# RoverMuxJig.net
KiCad netlist of a schematic drawn in EAGLE
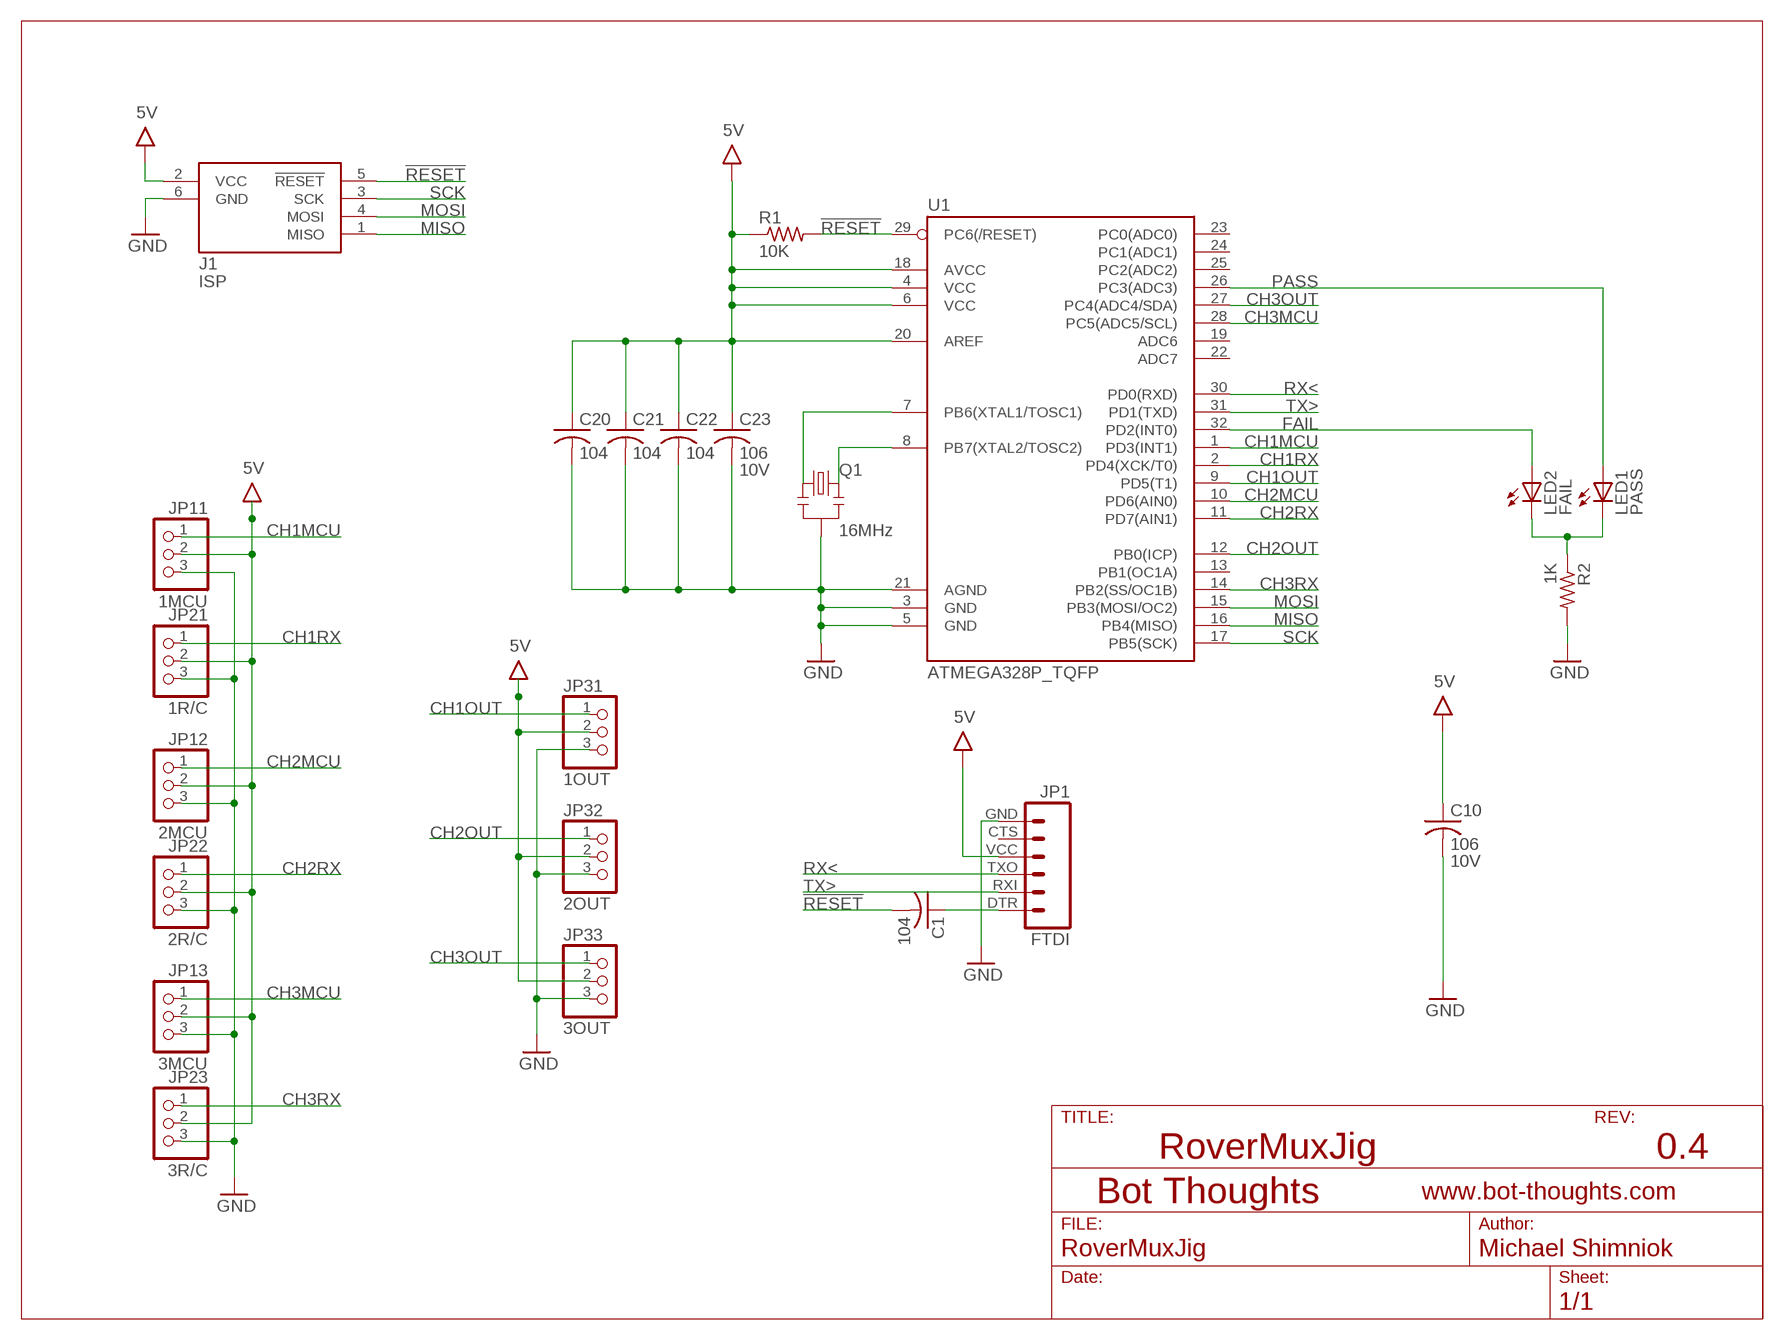
[diagram p0: schematic, sheet 1]

(export (version "E")
  (design (tool "Eeschema 10.0.6"))
  (components
    (comp (ref "C1")
      (value "104")
      (footprint "eagle-import:C0603")
      (fields (field (name "PARTNO") "C1608X7R1E104K080AA"))
      (libsource (lib "eagle-import") (part "C-USC0603"))
    )
    (comp (ref "C10")
      (value "106")
      (footprint "eagle-import:C0603")
      (fields (field (name "PARTNO") "CL10A106MP8NNNC") (field (name "VOLTAGE") "10V"))
      (libsource (lib "eagle-import") (part "C-USC0603"))
    )
    (comp (ref "C20")
      (value "104")
      (footprint "eagle-import:C0603")
      (fields (field (name "PARTNO") "C1608X7R1E104K080AA"))
      (libsource (lib "eagle-import") (part "C-USC0603"))
    )
    (comp (ref "C21")
      (value "104")
      (footprint "eagle-import:C0603")
      (fields (field (name "PARTNO") "C1608X7R1E104K080AA"))
      (libsource (lib "eagle-import") (part "C-USC0603"))
    )
    (comp (ref "C22")
      (value "104")
      (footprint "eagle-import:C0603")
      (fields (field (name "PARTNO") "C1608X7R1E104K080AA"))
      (libsource (lib "eagle-import") (part "C-USC0603"))
    )
    (comp (ref "C23")
      (value "106")
      (footprint "eagle-import:C0603")
      (fields (field (name "PARTNO") "CL10A106MP8NNNC") (field (name "VOLTAGE") "10V"))
      (libsource (lib "eagle-import") (part "C-USC0603"))
    )
    (comp (ref "J1")
      (value "ISP")
      (footprint "eagle-import:CON6P2R")
      (libsource (lib "eagle-import") (part "AVRISP6"))
    )
    (comp (ref "JP1")
      (value "FTDI")
      (footprint "eagle-import:FTDI_BASIC")
      (libsource (lib "eagle-import") (part "FTDI_BASICPTH"))
    )
    (comp (ref "JP11")
      (value "1MCU")
      (footprint "eagle-import:1X03-S")
      (libsource (lib "eagle-import") (part "PINHD-1X03_2.54-S"))
    )
    (comp (ref "JP12")
      (value "2MCU")
      (footprint "eagle-import:1X03-S")
      (libsource (lib "eagle-import") (part "PINHD-1X03_2.54-S"))
    )
    (comp (ref "JP13")
      (value "3MCU")
      (footprint "eagle-import:1X03-S")
      (libsource (lib "eagle-import") (part "PINHD-1X03_2.54-S"))
    )
    (comp (ref "JP21")
      (value "1R/C")
      (footprint "eagle-import:1X03-S")
      (libsource (lib "eagle-import") (part "PINHD-1X03_2.54-S"))
    )
    (comp (ref "JP22")
      (value "2R/C")
      (footprint "eagle-import:1X03-S")
      (libsource (lib "eagle-import") (part "PINHD-1X03_2.54-S"))
    )
    (comp (ref "JP23")
      (value "3R/C")
      (footprint "eagle-import:1X03-S")
      (libsource (lib "eagle-import") (part "PINHD-1X03_2.54-S"))
    )
    (comp (ref "JP31")
      (value "1OUT")
      (footprint "eagle-import:1X03-S")
      (libsource (lib "eagle-import") (part "PINHD-1X03_2.54-S"))
    )
    (comp (ref "JP32")
      (value "2OUT")
      (footprint "eagle-import:1X03-S")
      (libsource (lib "eagle-import") (part "PINHD-1X03_2.54-S"))
    )
    (comp (ref "JP33")
      (value "3OUT")
      (footprint "eagle-import:1X03-S")
      (libsource (lib "eagle-import") (part "PINHD-1X03_2.54-S"))
    )
    (comp (ref "LED1")
      (value "PASS")
      (footprint "eagle-import:CHIPLED_1206")
      (fields (field (name "PARTNO") "LH N974-KN-1"))
      (libsource (lib "eagle-import") (part "LEDCHIPLED_1206"))
    )
    (comp (ref "LED2")
      (value "FAIL")
      (footprint "eagle-import:CHIPLED_1206")
      (fields (field (name "PARTNO") "LG N971-KN-1"))
      (libsource (lib "eagle-import") (part "LEDCHIPLED_1206"))
    )
    (comp (ref "Q1")
      (value "16MHz")
      (footprint "eagle-import:CSTCE_V_C")
      (libsource (lib "eagle-import") (part "RESONATOR_CSTCE_V_C"))
    )
    (comp (ref "R1")
      (value "10K")
      (footprint "eagle-import:R0603")
      (fields (field (name "PARTNO") "RC0603JR-07330RL"))
      (libsource (lib "eagle-import") (part "R-US_R0603"))
    )
    (comp (ref "R2")
      (value "1K")
      (footprint "eagle-import:R0603")
      (fields (field (name "PARTNO") "RC0603JR-07330RL"))
      (libsource (lib "eagle-import") (part "R-US_R0603"))
    )
    (comp (ref "U1")
      (value "ATMEGA328P_TQFP")
      (footprint "eagle-import:TQFP32-08")
      (libsource (lib "eagle-import") (part "ATMEGA328P_TQFP"))
    )
  )
  (nets
    (net (code "1") (name "/CH1MCU") (class "Default")
      (node (ref "JP11") (pin "1") (pinfunction "1_1") (pintype "passive"))
      (node (ref "U1") (pin "1") (pinfunction "PD3(INT1)_1") (pintype "bidirectional"))
    )
    (net (code "2") (name "/CH1OUT") (class "Default")
      (node (ref "JP31") (pin "1") (pinfunction "1_1") (pintype "passive"))
      (node (ref "U1") (pin "9") (pinfunction "PD5(T1)_9") (pintype "bidirectional"))
    )
    (net (code "3") (name "/CH1RX") (class "Default")
      (node (ref "JP21") (pin "1") (pinfunction "1_1") (pintype "passive"))
      (node (ref "U1") (pin "2") (pinfunction "PD4(XCK/T0)_2") (pintype "bidirectional"))
    )
    (net (code "4") (name "/CH2MCU") (class "Default")
      (node (ref "JP12") (pin "1") (pinfunction "1_1") (pintype "passive"))
      (node (ref "U1") (pin "10") (pinfunction "PD6(AIN0)_10") (pintype "bidirectional"))
    )
    (net (code "5") (name "/CH2OUT") (class "Default")
      (node (ref "JP32") (pin "1") (pinfunction "1_1") (pintype "passive"))
      (node (ref "U1") (pin "12") (pinfunction "PB0(ICP)_12") (pintype "bidirectional"))
    )
    (net (code "6") (name "/CH2RX") (class "Default")
      (node (ref "JP22") (pin "1") (pinfunction "1_1") (pintype "passive"))
      (node (ref "U1") (pin "11") (pinfunction "PD7(AIN1)_11") (pintype "bidirectional"))
    )
    (net (code "7") (name "/CH3MCU") (class "Default")
      (node (ref "JP13") (pin "1") (pinfunction "1_1") (pintype "passive"))
      (node (ref "U1") (pin "28") (pinfunction "PC5(ADC5/SCL)_28") (pintype "bidirectional"))
    )
    (net (code "8") (name "/CH3OUT") (class "Default")
      (node (ref "JP33") (pin "1") (pinfunction "1_1") (pintype "passive"))
      (node (ref "U1") (pin "27") (pinfunction "PC4(ADC4/SDA)_27") (pintype "bidirectional"))
    )
    (net (code "9") (name "/CH3RX") (class "Default")
      (node (ref "JP23") (pin "1") (pinfunction "1_1") (pintype "passive"))
      (node (ref "U1") (pin "14") (pinfunction "PB2(SS/OC1B)_14") (pintype "bidirectional"))
    )
    (net (code "10") (name "/FAIL") (class "Default")
      (node (ref "LED2") (pin "A") (pinfunction "A_A") (pintype "passive"))
      (node (ref "U1") (pin "32") (pinfunction "PD2(INT0)_32") (pintype "bidirectional"))
    )
    (net (code "11") (name "/MISO") (class "Default")
      (node (ref "J1") (pin "1") (pinfunction "MISO_1") (pintype "input"))
      (node (ref "U1") (pin "16") (pinfunction "PB4(MISO)_16") (pintype "bidirectional"))
    )
    (net (code "12") (name "/MOSI") (class "Default")
      (node (ref "J1") (pin "4") (pinfunction "MOSI_4") (pintype "output"))
      (node (ref "U1") (pin "15") (pinfunction "PB3(MOSI/OC2)_15") (pintype "bidirectional"))
    )
    (net (code "13") (name "/PASS") (class "Default")
      (node (ref "LED1") (pin "A") (pinfunction "A_A") (pintype "passive"))
      (node (ref "U1") (pin "26") (pinfunction "PC3(ADC3)_26") (pintype "bidirectional"))
    )
    (net (code "14") (name "/RX<") (class "Default")
      (node (ref "JP1") (pin "TXO") (pinfunction "3_TXO") (pintype "passive"))
      (node (ref "U1") (pin "30") (pinfunction "PD0(RXD)_30") (pintype "bidirectional"))
    )
    (net (code "15") (name "/SCK") (class "Default")
      (node (ref "J1") (pin "3") (pinfunction "SCK_3") (pintype "output"))
      (node (ref "U1") (pin "17") (pinfunction "PB5(SCK)_17") (pintype "bidirectional"))
    )
    (net (code "16") (name "/TX>") (class "Default")
      (node (ref "JP1") (pin "RXI") (pinfunction "2_RXI") (pintype "passive"))
      (node (ref "U1") (pin "31") (pinfunction "PD1(TXD)_31") (pintype "bidirectional"))
    )
    (net (code "17") (name "/~{RESET}") (class "Default")
      (node (ref "C1") (pin "2") (pinfunction "2_2") (pintype "passive"))
      (node (ref "J1") (pin "5") (pinfunction "~{RESET}_5") (pintype "output"))
      (node (ref "R1") (pin "2") (pinfunction "2_2") (pintype "passive"))
      (node (ref "U1") (pin "29") (pinfunction "PC6(/RESET)_29") (pintype "bidirectional"))
    )
    (net (code "18") (name "5V") (class "Default")
      (node (ref "C10") (pin "1") (pinfunction "1_1") (pintype "passive"))
      (node (ref "C20") (pin "1") (pinfunction "1_1") (pintype "passive"))
      (node (ref "C21") (pin "1") (pinfunction "1_1") (pintype "passive"))
      (node (ref "C22") (pin "1") (pinfunction "1_1") (pintype "passive"))
      (node (ref "C23") (pin "1") (pinfunction "1_1") (pintype "passive"))
      (node (ref "J1") (pin "2") (pinfunction "VCC_2") (pintype "power_in"))
      (node (ref "JP1") (pin "VCC") (pinfunction "4_VCC") (pintype "passive"))
      (node (ref "JP11") (pin "2") (pinfunction "2_2") (pintype "passive"))
      (node (ref "JP12") (pin "2") (pinfunction "2_2") (pintype "passive"))
      (node (ref "JP13") (pin "2") (pinfunction "2_2") (pintype "passive"))
      (node (ref "JP21") (pin "2") (pinfunction "2_2") (pintype "passive"))
      (node (ref "JP22") (pin "2") (pinfunction "2_2") (pintype "passive"))
      (node (ref "JP23") (pin "2") (pinfunction "2_2") (pintype "passive"))
      (node (ref "JP31") (pin "2") (pinfunction "2_2") (pintype "passive"))
      (node (ref "JP32") (pin "2") (pinfunction "2_2") (pintype "passive"))
      (node (ref "JP33") (pin "2") (pinfunction "2_2") (pintype "passive"))
      (node (ref "R1") (pin "1") (pinfunction "1_1") (pintype "passive"))
      (node (ref "U1") (pin "18") (pinfunction "AVCC_18") (pintype "bidirectional"))
      (node (ref "U1") (pin "20") (pinfunction "AREF_20") (pintype "bidirectional"))
      (node (ref "U1") (pin "4") (pinfunction "VCC_4") (pintype "bidirectional"))
      (node (ref "U1") (pin "6") (pinfunction "VCC_6") (pintype "bidirectional"))
    )
    (net (code "19") (name "GND") (class "Default")
      (node (ref "C10") (pin "2") (pinfunction "2_2") (pintype "passive"))
      (node (ref "C20") (pin "2") (pinfunction "2_2") (pintype "passive"))
      (node (ref "C21") (pin "2") (pinfunction "2_2") (pintype "passive"))
      (node (ref "C22") (pin "2") (pinfunction "2_2") (pintype "passive"))
      (node (ref "C23") (pin "2") (pinfunction "2_2") (pintype "passive"))
      (node (ref "J1") (pin "6") (pinfunction "GND_6") (pintype "power_in"))
      (node (ref "JP1") (pin "GND") (pinfunction "6_GND") (pintype "passive"))
      (node (ref "JP11") (pin "3") (pinfunction "3_3") (pintype "passive"))
      (node (ref "JP12") (pin "3") (pinfunction "3_3") (pintype "passive"))
      (node (ref "JP13") (pin "3") (pinfunction "3_3") (pintype "passive"))
      (node (ref "JP21") (pin "3") (pinfunction "3_3") (pintype "passive"))
      (node (ref "JP22") (pin "3") (pinfunction "3_3") (pintype "passive"))
      (node (ref "JP23") (pin "3") (pinfunction "3_3") (pintype "passive"))
      (node (ref "JP31") (pin "3") (pinfunction "3_3") (pintype "passive"))
      (node (ref "JP32") (pin "3") (pinfunction "3_3") (pintype "passive"))
      (node (ref "JP33") (pin "3") (pinfunction "3_3") (pintype "passive"))
      (node (ref "Q1") (pin "GND") (pinfunction "GND_GND") (pintype "passive"))
      (node (ref "R2") (pin "2") (pinfunction "2_2") (pintype "passive"))
      (node (ref "U1") (pin "21") (pinfunction "AGND_21") (pintype "bidirectional"))
      (node (ref "U1") (pin "3") (pinfunction "GND_3") (pintype "bidirectional"))
      (node (ref "U1") (pin "5") (pinfunction "GND_5") (pintype "bidirectional"))
    )
    (net (code "20") (name "Net-(JP1-1)") (class "Default")
      (node (ref "C1") (pin "1") (pinfunction "1_1") (pintype "passive"))
      (node (ref "JP1") (pin "DTR") (pinfunction "1_DTR") (pintype "passive"))
    )
    (net (code "21") (name "Net-(LED1-PadC)") (class "Default")
      (node (ref "LED1") (pin "C") (pinfunction "C_C") (pintype "passive"))
      (node (ref "LED2") (pin "C") (pinfunction "C_C") (pintype "passive"))
      (node (ref "R2") (pin "1") (pinfunction "1_1") (pintype "passive"))
    )
    (net (code "22") (name "Net-(U1-PB6(XTAL1{slash}TOSC1))") (class "Default")
      (node (ref "Q1") (pin "X1") (pinfunction "X1_X1") (pintype "passive"))
      (node (ref "U1") (pin "7") (pinfunction "PB6(XTAL1/TOSC1)_7") (pintype "bidirectional"))
    )
    (net (code "23") (name "Net-(U1-PB7(XTAL2{slash}TOSC2))") (class "Default")
      (node (ref "Q1") (pin "X2") (pinfunction "X2_X2") (pintype "passive"))
      (node (ref "U1") (pin "8") (pinfunction "PB7(XTAL2/TOSC2)_8") (pintype "bidirectional"))
    )
    (net (code "24") (name "unconnected-(JP1-5-PadCTS)") (class "Default")
      (node (ref "JP1") (pin "CTS") (pinfunction "5_CTS") (pintype "passive"))
    )
    (net (code "25") (name "unconnected-(U1-ADC6-Pad19)") (class "Default")
      (node (ref "U1") (pin "19") (pinfunction "ADC6_19") (pintype "bidirectional"))
    )
    (net (code "26") (name "unconnected-(U1-ADC7-Pad22)") (class "Default")
      (node (ref "U1") (pin "22") (pinfunction "ADC7_22") (pintype "bidirectional"))
    )
    (net (code "27") (name "unconnected-(U1-PB1(OC1A)-Pad13)") (class "Default")
      (node (ref "U1") (pin "13") (pinfunction "PB1(OC1A)_13") (pintype "bidirectional"))
    )
    (net (code "28") (name "unconnected-(U1-PC0(ADC0)-Pad23)") (class "Default")
      (node (ref "U1") (pin "23") (pinfunction "PC0(ADC0)_23") (pintype "bidirectional"))
    )
    (net (code "29") (name "unconnected-(U1-PC1(ADC1)-Pad24)") (class "Default")
      (node (ref "U1") (pin "24") (pinfunction "PC1(ADC1)_24") (pintype "bidirectional"))
    )
    (net (code "30") (name "unconnected-(U1-PC2(ADC2)-Pad25)") (class "Default")
      (node (ref "U1") (pin "25") (pinfunction "PC2(ADC2)_25") (pintype "bidirectional"))
    )
  )
)
